# MeteoStationNucleo.net
KiCad netlist of a schematic drawn in Altium Designer
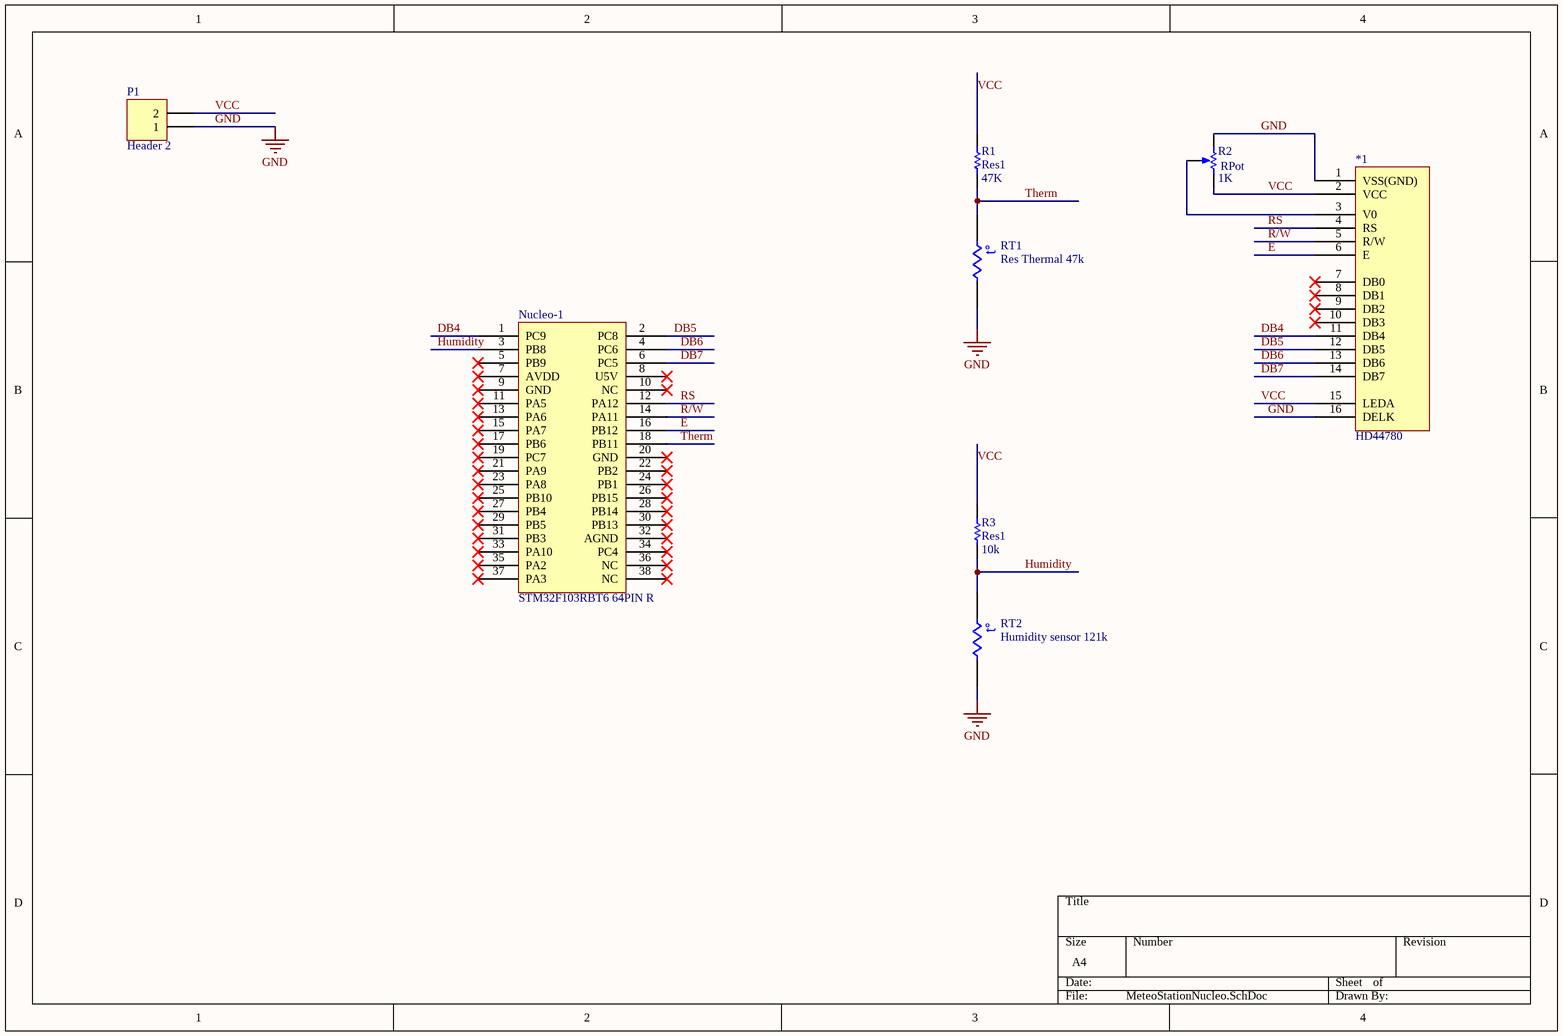
[diagram p0: MeteoStationNucleo.SchDoc]

(export (version "E")
  (design (tool "Eeschema 10.0.6"))
  (components
    (comp (ref "*1") (value "HD44780") (libsource (lib "MeteoStationNucleo") (part "HD44780")))
    (comp (ref "Nucleo-1")
      (value "STM32F103RBT6 64PIN R")
      (description "Right side")
      (libsource (lib "MeteoStationNucleo") (part "STM32F103RBT6 64PIN R"))
    )
    (comp (ref "P1")
      (value "Header 2")
      (footprint "HDR1X2")
      (description "Header, 2-Pin")
      (fields (field (name "PUBLISHER") "Altium Limited"))
      (libsource (lib "Miscellaneous Connectors") (part "Header 2"))
    )
    (comp (ref "R1")
      (value "Res1")
      (footprint "AXIAL-0.3")
      (description "Resistor")
      (fields (field (name "ALTIUM_VALUE") "47K") (field (name "PUBLISHER") "Altium Limited"))
      (libsource (lib "Miscellaneous Devices") (part "Res1"))
    )
    (comp (ref "R2")
      (value "RPot")
      (footprint "VR5")
      (description "Potentiometer")
      (fields (field (name "ALTIUM_VALUE") "1K") (field (name "PUBLISHER") "Altium Limited"))
      (libsource (lib "Miscellaneous Devices") (part "RPot"))
    )
    (comp (ref "R3")
      (value "Res1")
      (footprint "AXIAL-0.3")
      (description "Resistor")
      (fields (field (name "ALTIUM_VALUE") "10k") (field (name "PUBLISHER") "Altium Limited"))
      (libsource (lib "Miscellaneous Devices") (part "Res1"))
    )
    (comp (ref "RT1")
      (value "Res Thermal 47k")
      (footprint "6-0805_N")
      (description "Thermistor")
      (fields (field (name "PUBLISHER") "Altium Limited"))
      (libsource (lib "Miscellaneous Devices") (part "Res Thermal"))
    )
    (comp (ref "RT2")
      (value "Humidity sensor 121k")
      (footprint "6-0805_N")
      (description "Thermistor")
      (fields (field (name "PUBLISHER") "Altium Limited"))
      (libsource (lib "Miscellaneous Devices") (part "Res Thermal"))
    )
  )
  (nets
    (net (code "1") (name "/DB4") (class "Default")
      (node (ref "*1") (pin "11") (pinfunction "DB4_11") (pintype "passive"))
      (node (ref "Nucleo-1") (pin "1") (pinfunction "PC9_1") (pintype "passive"))
    )
    (net (code "2") (name "/DB5") (class "Default")
      (node (ref "*1") (pin "12") (pinfunction "DB5_12") (pintype "passive"))
      (node (ref "Nucleo-1") (pin "2") (pinfunction "PC8_2") (pintype "passive"))
    )
    (net (code "3") (name "/DB6") (class "Default")
      (node (ref "*1") (pin "13") (pinfunction "DB6_13") (pintype "passive"))
      (node (ref "Nucleo-1") (pin "4") (pinfunction "PC6_4") (pintype "passive"))
    )
    (net (code "4") (name "/DB7") (class "Default")
      (node (ref "*1") (pin "14") (pinfunction "DB7_14") (pintype "passive"))
      (node (ref "Nucleo-1") (pin "6") (pinfunction "PC5_6") (pintype "passive"))
    )
    (net (code "5") (name "/E") (class "Default")
      (node (ref "*1") (pin "6") (pinfunction "E_6") (pintype "passive"))
      (node (ref "Nucleo-1") (pin "16") (pinfunction "PB12_16") (pintype "passive"))
    )
    (net (code "6") (name "/Humidity") (class "Default")
      (node (ref "Nucleo-1") (pin "3") (pinfunction "PB8_3") (pintype "passive"))
      (node (ref "R3") (pin "1") (pinfunction "1_1") (pintype "passive"))
      (node (ref "RT2") (pin "1") (pinfunction "1_1") (pintype "passive"))
    )
    (net (code "7") (name "/RS") (class "Default")
      (node (ref "*1") (pin "4") (pinfunction "RS_4") (pintype "passive"))
      (node (ref "Nucleo-1") (pin "12") (pinfunction "PA12_12") (pintype "passive"))
    )
    (net (code "8") (name "/R{slash}W") (class "Default")
      (node (ref "*1") (pin "5") (pinfunction "R/W_5") (pintype "passive"))
      (node (ref "Nucleo-1") (pin "14") (pinfunction "PA11_14") (pintype "passive"))
    )
    (net (code "9") (name "/Therm") (class "Default")
      (node (ref "Nucleo-1") (pin "18") (pinfunction "PB11_18") (pintype "passive"))
      (node (ref "R1") (pin "1") (pinfunction "1_1") (pintype "passive"))
      (node (ref "RT1") (pin "1") (pinfunction "1_1") (pintype "passive"))
    )
    (net (code "10") (name "/VCC") (class "Default")
      (node (ref "*1") (pin "15") (pinfunction "LEDA_15") (pintype "passive"))
      (node (ref "*1") (pin "2") (pinfunction "VCC_2") (pintype "passive"))
      (node (ref "P1") (pin "2") (pinfunction "2_2") (pintype "passive"))
      (node (ref "R1") (pin "2") (pinfunction "2_2") (pintype "passive"))
      (node (ref "R2") (pin "2") (pinfunction "BOT_2") (pintype "passive"))
      (node (ref "R3") (pin "2") (pinfunction "2_2") (pintype "passive"))
    )
    (net (code "11") (name "GND") (class "Default")
      (node (ref "*1") (pin "1") (pinfunction "VSS(GND)_1") (pintype "passive"))
      (node (ref "*1") (pin "16") (pinfunction "DELK_16") (pintype "passive"))
      (node (ref "P1") (pin "1") (pinfunction "1_1") (pintype "passive"))
      (node (ref "R2") (pin "1") (pinfunction "TOP_1") (pintype "passive"))
      (node (ref "RT1") (pin "2") (pinfunction "2_2") (pintype "passive"))
      (node (ref "RT2") (pin "2") (pinfunction "2_2") (pintype "passive"))
    )
    (net (code "12") (name "Net-(*1-V0)") (class "Default")
      (node (ref "*1") (pin "3") (pinfunction "V0_3") (pintype "passive"))
      (node (ref "R2") (pin "3") (pinfunction "TAP_3") (pintype "passive"))
    )
    (net (code "13") (name "unconnected-(*1-DB0-Pad7)") (class "Default")
      (node (ref "*1") (pin "7") (pinfunction "DB0_7") (pintype "passive+no_connect"))
    )
    (net (code "14") (name "unconnected-(*1-DB1-Pad8)") (class "Default")
      (node (ref "*1") (pin "8") (pinfunction "DB1_8") (pintype "passive+no_connect"))
    )
    (net (code "15") (name "unconnected-(*1-DB2-Pad9)") (class "Default")
      (node (ref "*1") (pin "9") (pinfunction "DB2_9") (pintype "passive+no_connect"))
    )
    (net (code "16") (name "unconnected-(*1-DB3-Pad10)") (class "Default")
      (node (ref "*1") (pin "10") (pinfunction "DB3_10") (pintype "passive+no_connect"))
    )
    (net (code "17") (name "unconnected-(Nucleo-1-AGND-Pad32)") (class "Default")
      (node (ref "Nucleo-1") (pin "32") (pinfunction "AGND_32") (pintype "passive+no_connect"))
    )
    (net (code "18") (name "unconnected-(Nucleo-1-AVDD-Pad7)") (class "Default")
      (node (ref "Nucleo-1") (pin "7") (pinfunction "AVDD_7") (pintype "passive+no_connect"))
    )
    (net (code "19") (name "unconnected-(Nucleo-1-GND-Pad9)") (class "Default")
      (node (ref "Nucleo-1") (pin "9") (pinfunction "GND_9") (pintype "passive+no_connect"))
    )
    (net (code "20") (name "unconnected-(Nucleo-1-GND-Pad20)") (class "Default")
      (node (ref "Nucleo-1") (pin "20") (pinfunction "GND_20") (pintype "passive+no_connect"))
    )
    (net (code "21") (name "unconnected-(Nucleo-1-NC-Pad10)") (class "Default")
      (node (ref "Nucleo-1") (pin "10") (pinfunction "NC_10") (pintype "passive+no_connect"))
    )
    (net (code "22") (name "unconnected-(Nucleo-1-NC-Pad36)") (class "Default")
      (node (ref "Nucleo-1") (pin "36") (pinfunction "NC_36") (pintype "passive+no_connect"))
    )
    (net (code "23") (name "unconnected-(Nucleo-1-NC-Pad38)") (class "Default")
      (node (ref "Nucleo-1") (pin "38") (pinfunction "NC_38") (pintype "passive+no_connect"))
    )
    (net (code "24") (name "unconnected-(Nucleo-1-PA2-Pad35)") (class "Default")
      (node (ref "Nucleo-1") (pin "35") (pinfunction "PA2_35") (pintype "passive+no_connect"))
    )
    (net (code "25") (name "unconnected-(Nucleo-1-PA3-Pad37)") (class "Default")
      (node (ref "Nucleo-1") (pin "37") (pinfunction "PA3_37") (pintype "passive+no_connect"))
    )
    (net (code "26") (name "unconnected-(Nucleo-1-PA5-Pad11)") (class "Default")
      (node (ref "Nucleo-1") (pin "11") (pinfunction "PA5_11") (pintype "passive+no_connect"))
    )
    (net (code "27") (name "unconnected-(Nucleo-1-PA6-Pad13)") (class "Default")
      (node (ref "Nucleo-1") (pin "13") (pinfunction "PA6_13") (pintype "passive+no_connect"))
    )
    (net (code "28") (name "unconnected-(Nucleo-1-PA7-Pad15)") (class "Default")
      (node (ref "Nucleo-1") (pin "15") (pinfunction "PA7_15") (pintype "passive+no_connect"))
    )
    (net (code "29") (name "unconnected-(Nucleo-1-PA8-Pad23)") (class "Default")
      (node (ref "Nucleo-1") (pin "23") (pinfunction "PA8_23") (pintype "passive+no_connect"))
    )
    (net (code "30") (name "unconnected-(Nucleo-1-PA9-Pad21)") (class "Default")
      (node (ref "Nucleo-1") (pin "21") (pinfunction "PA9_21") (pintype "passive+no_connect"))
    )
    (net (code "31") (name "unconnected-(Nucleo-1-PA10-Pad33)") (class "Default")
      (node (ref "Nucleo-1") (pin "33") (pinfunction "PA10_33") (pintype "passive+no_connect"))
    )
    (net (code "32") (name "unconnected-(Nucleo-1-PB1-Pad24)") (class "Default")
      (node (ref "Nucleo-1") (pin "24") (pinfunction "PB1_24") (pintype "passive+no_connect"))
    )
    (net (code "33") (name "unconnected-(Nucleo-1-PB2-Pad22)") (class "Default")
      (node (ref "Nucleo-1") (pin "22") (pinfunction "PB2_22") (pintype "passive+no_connect"))
    )
    (net (code "34") (name "unconnected-(Nucleo-1-PB3-Pad31)") (class "Default")
      (node (ref "Nucleo-1") (pin "31") (pinfunction "PB3_31") (pintype "passive+no_connect"))
    )
    (net (code "35") (name "unconnected-(Nucleo-1-PB4-Pad27)") (class "Default")
      (node (ref "Nucleo-1") (pin "27") (pinfunction "PB4_27") (pintype "passive+no_connect"))
    )
    (net (code "36") (name "unconnected-(Nucleo-1-PB5-Pad29)") (class "Default")
      (node (ref "Nucleo-1") (pin "29") (pinfunction "PB5_29") (pintype "passive+no_connect"))
    )
    (net (code "37") (name "unconnected-(Nucleo-1-PB6-Pad17)") (class "Default")
      (node (ref "Nucleo-1") (pin "17") (pinfunction "PB6_17") (pintype "passive+no_connect"))
    )
    (net (code "38") (name "unconnected-(Nucleo-1-PB9-Pad5)") (class "Default")
      (node (ref "Nucleo-1") (pin "5") (pinfunction "PB9_5") (pintype "passive+no_connect"))
    )
    (net (code "39") (name "unconnected-(Nucleo-1-PB10-Pad25)") (class "Default")
      (node (ref "Nucleo-1") (pin "25") (pinfunction "PB10_25") (pintype "passive+no_connect"))
    )
    (net (code "40") (name "unconnected-(Nucleo-1-PB13-Pad30)") (class "Default")
      (node (ref "Nucleo-1") (pin "30") (pinfunction "PB13_30") (pintype "passive+no_connect"))
    )
    (net (code "41") (name "unconnected-(Nucleo-1-PB14-Pad28)") (class "Default")
      (node (ref "Nucleo-1") (pin "28") (pinfunction "PB14_28") (pintype "passive+no_connect"))
    )
    (net (code "42") (name "unconnected-(Nucleo-1-PB15-Pad26)") (class "Default")
      (node (ref "Nucleo-1") (pin "26") (pinfunction "PB15_26") (pintype "passive+no_connect"))
    )
    (net (code "43") (name "unconnected-(Nucleo-1-PC4-Pad34)") (class "Default")
      (node (ref "Nucleo-1") (pin "34") (pinfunction "PC4_34") (pintype "passive+no_connect"))
    )
    (net (code "44") (name "unconnected-(Nucleo-1-PC7-Pad19)") (class "Default")
      (node (ref "Nucleo-1") (pin "19") (pinfunction "PC7_19") (pintype "passive+no_connect"))
    )
    (net (code "45") (name "unconnected-(Nucleo-1-U5V-Pad8)") (class "Default")
      (node (ref "Nucleo-1") (pin "8") (pinfunction "U5V_8") (pintype "passive+no_connect"))
    )
  )
)
